# ultrasonic.net
KiCad netlist of a schematic drawn in Altium Designer
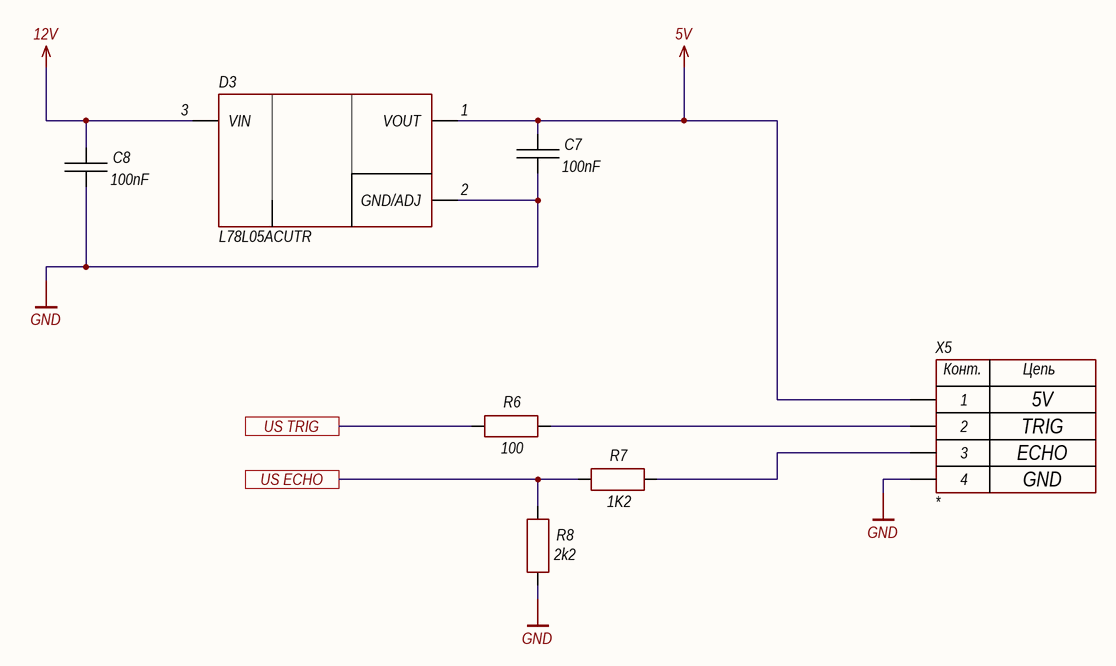
[diagram p0: ultrasonic.SchDoc]

(export (version "E")
  (design (tool "Eeschema 10.0.6"))
  (components
    (comp (ref "C7") (value "100nF") (footprint "CH0603C") (libsource (lib "Discrete") (part "Capacitor")))
    (comp (ref "C8") (value "100nF") (footprint "CH0603C") (libsource (lib "Discrete") (part "Capacitor")))
    (comp (ref "D3")
      (value "L78L05ACUTR")
      (footprint "SOT89_123")
      (description "Step-down")
      (fields (field (name "MANUFACTURER") "ST Microelectronics"))
      (libsource (lib "Power Supplies") (part "L78LxxACUTR"))
    )
    (comp (ref "R6") (value "100") (footprint "CH0603R") (libsource (lib "Discrete") (part "Resistor")))
    (comp (ref "R7") (value "1K2") (footprint "CH0603R") (libsource (lib "Discrete") (part "Resistor")))
    (comp (ref "R8") (value "2k2") (footprint "CH0603R") (libsource (lib "") (part "Resistor_1")))
    (comp (ref "X5") (value "*") (footprint "CON: PBS-4") (libsource (lib "Connectors") (part "4-Connector")))
  )
  (nets
    (net (code "1") (name "/US ECHO") (class "Default")
      (node (ref "R7") (pin "1") (pinfunction "1_1") (pintype "passive"))
      (node (ref "R8") (pin "2") (pinfunction "2_2") (pintype "passive"))
    )
    (net (code "2") (name "/US TRIG") (class "Default")
      (node (ref "R6") (pin "1") (pinfunction "1_1") (pintype "passive"))
    )
    (net (code "3") (name "5V") (class "Default")
      (node (ref "C7") (pin "2") (pinfunction "2_2") (pintype "power_in"))
      (node (ref "D3") (pin "1") (pinfunction "VOUT_1") (pintype "power_in"))
      (node (ref "X5") (pin "1") (pinfunction "1_1") (pintype "passive"))
    )
    (net (code "4") (name "12V") (class "Default")
      (node (ref "C8") (pin "2") (pinfunction "2_2") (pintype "power_in"))
      (node (ref "D3") (pin "3") (pinfunction "VIN_3") (pintype "power_in"))
    )
    (net (code "5") (name "GND") (class "Default")
      (node (ref "C7") (pin "1") (pinfunction "1_1") (pintype "power_in"))
      (node (ref "C8") (pin "1") (pinfunction "1_1") (pintype "power_in"))
      (node (ref "D3") (pin "2") (pinfunction "GND/ADJ_2") (pintype "power_in"))
      (node (ref "R8") (pin "1") (pinfunction "1_1") (pintype "passive"))
      (node (ref "X5") (pin "4") (pinfunction "4_4") (pintype "power_in"))
    )
    (net (code "6") (name "Net-(R6-Pad2)") (class "Default")
      (node (ref "R6") (pin "2") (pinfunction "2_2") (pintype "passive"))
      (node (ref "X5") (pin "2") (pinfunction "2_2") (pintype "passive"))
    )
    (net (code "7") (name "Net-(R7-Pad2)") (class "Default")
      (node (ref "R7") (pin "2") (pinfunction "2_2") (pintype "passive"))
      (node (ref "X5") (pin "3") (pinfunction "3_3") (pintype "power_in"))
    )
  )
)
